# PICZone.net
KiCad netlist of a schematic drawn in Altium Designer
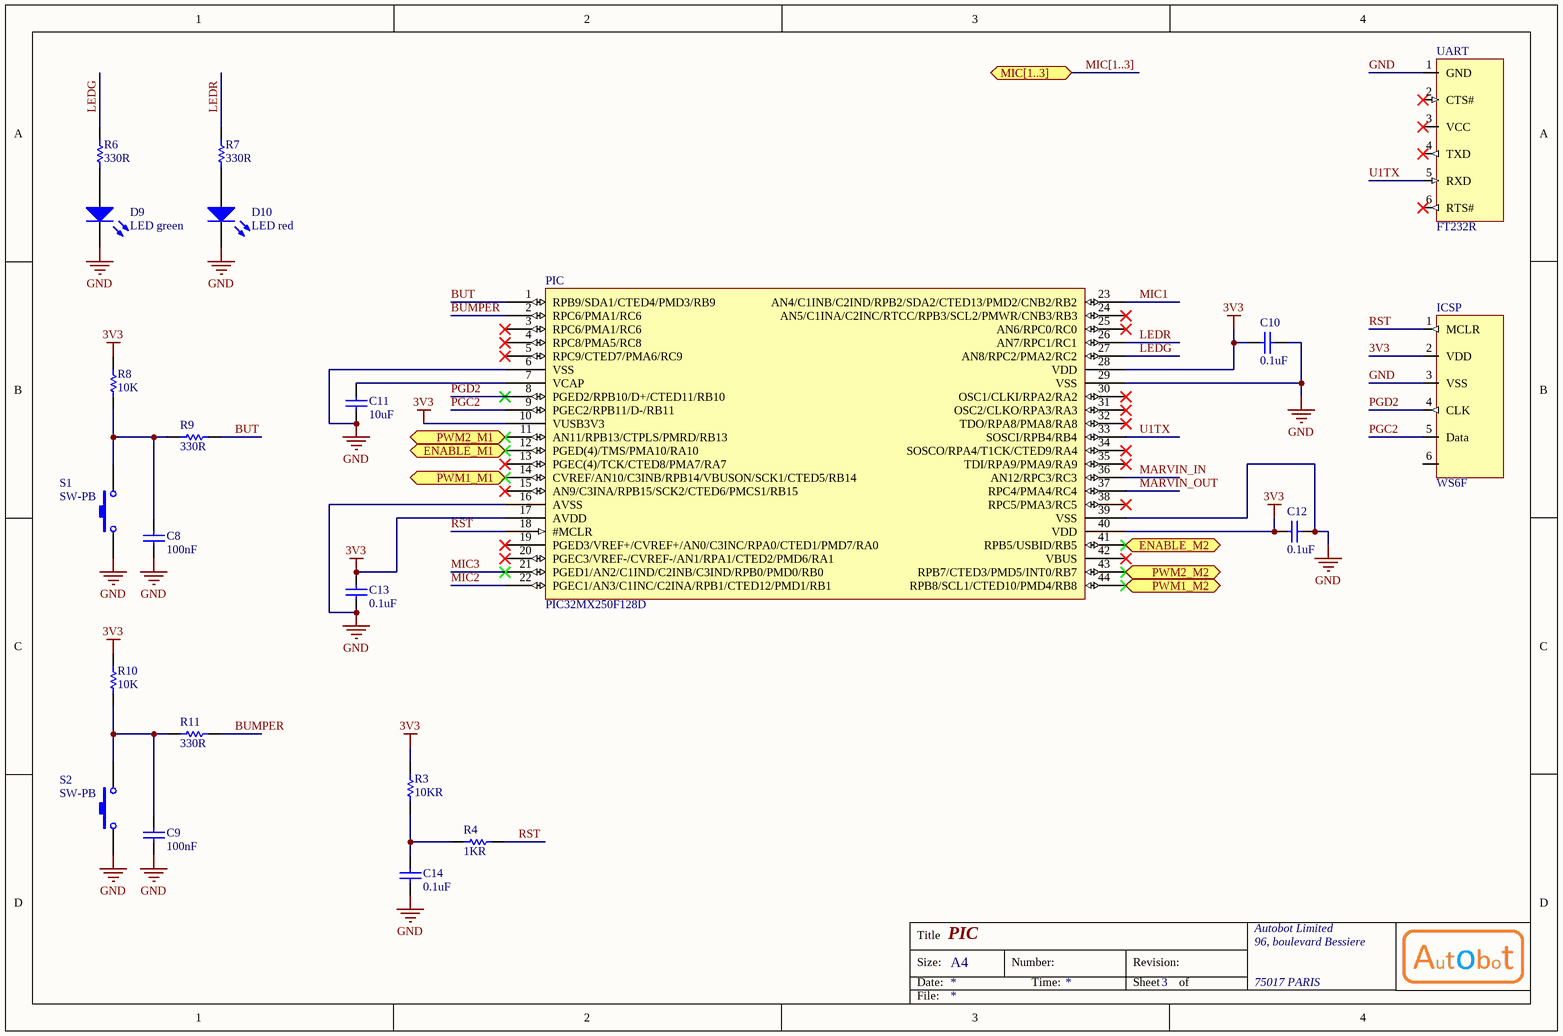
[diagram p0: PICZone.SchDoc]

(export (version "E")
  (design (tool "Eeschema 10.0.6"))
  (components
    (comp (ref "C8")
      (value "100nF")
      (footprint "CAPC1608N")
      (description "Capacitor")
      (fields (field (name "PUBLISHER") "Altium Limited"))
      (libsource (lib "Miscellaneous Devices") (part "Cap"))
    )
    (comp (ref "C9")
      (value "100nF")
      (footprint "CAPC1608N")
      (description "Capacitor")
      (fields (field (name "PUBLISHER") "Altium Limited"))
      (libsource (lib "Miscellaneous Devices") (part "Cap"))
    )
    (comp (ref "C10")
      (value "0.1uF")
      (footprint "CAPC1608N")
      (description "Capacitor")
      (fields (field (name "PUBLISHER") "Altium Limited"))
      (libsource (lib "Miscellaneous Devices") (part "Cap"))
    )
    (comp (ref "C11")
      (value "10uF")
      (footprint "CAPC1608N")
      (description "Capacitor")
      (fields (field (name "PUBLISHER") "Altium Limited"))
      (libsource (lib "Miscellaneous Devices") (part "Cap"))
    )
    (comp (ref "C12")
      (value "0.1uF")
      (footprint "CAPC1608N")
      (description "Capacitor")
      (fields (field (name "PUBLISHER") "Altium Limited"))
      (libsource (lib "Miscellaneous Devices") (part "Cap"))
    )
    (comp (ref "C13")
      (value "0.1uF")
      (footprint "CAPC1608N")
      (description "Capacitor")
      (fields (field (name "PUBLISHER") "Altium Limited"))
      (libsource (lib "Miscellaneous Devices") (part "Cap"))
    )
    (comp (ref "C14")
      (value "0.1uF")
      (footprint "CAPC1608N")
      (description "Capacitor")
      (fields (field (name "PUBLISHER") "Altium Limited"))
      (libsource (lib "Miscellaneous Devices") (part "Cap"))
    )
    (comp (ref "D9")
      (value "LED green")
      (footprint "LED1608")
      (description "Typical INFRARED GaAs LED")
      (fields (field (name "PUBLISHER") "Altium Limited"))
      (libsource (lib "Miscellaneous Devices") (part "LED0"))
    )
    (comp (ref "D10")
      (value "LED red")
      (footprint "LED1608")
      (description "Typical INFRARED GaAs LED")
      (fields (field (name "PUBLISHER") "Altium Limited"))
      (libsource (lib "Miscellaneous Devices") (part "LED0"))
    )
    (comp (ref "ICSP")
      (value "WS6F")
      (footprint "6-pin Connector")
      (libsource (lib "SCHLIB_Autobot") (part "WS6F"))
    )
    (comp (ref "PIC")
      (value "PIC32MX250F128D")
      (footprint "44TQFP")
      (libsource (lib "SCHLIB_Autobot") (part "PIC32MX250F128D"))
    )
    (comp (ref "R3")
      (value "10KR")
      (footprint "RESC1608N")
      (description "Resistor")
      (fields (field (name "PUBLISHER") "Altium Limited"))
      (libsource (lib "Miscellaneous Devices") (part "Res1"))
    )
    (comp (ref "R4")
      (value "1KR")
      (footprint "RESC1608N")
      (description "Resistor")
      (fields (field (name "PUBLISHER") "Altium Limited"))
      (libsource (lib "Miscellaneous Devices") (part "Res1"))
    )
    (comp (ref "R6")
      (value "330R")
      (footprint "RESC1608N")
      (description "Resistor")
      (fields (field (name "PUBLISHER") "Altium Limited"))
      (libsource (lib "Miscellaneous Devices") (part "Res1"))
    )
    (comp (ref "R7")
      (value "330R")
      (footprint "RESC1608N")
      (description "Resistor")
      (fields (field (name "PUBLISHER") "Altium Limited"))
      (libsource (lib "Miscellaneous Devices") (part "Res1"))
    )
    (comp (ref "R8")
      (value "10K")
      (footprint "RESC1608N")
      (description "Resistor")
      (fields (field (name "PUBLISHER") "Altium Limited"))
      (libsource (lib "Miscellaneous Devices") (part "Res1"))
    )
    (comp (ref "R9")
      (value "330R")
      (footprint "RESC1608N")
      (description "Resistor")
      (fields (field (name "PUBLISHER") "Altium Limited"))
      (libsource (lib "Miscellaneous Devices") (part "Res1"))
    )
    (comp (ref "R10")
      (value "10K")
      (footprint "RESC1608N")
      (description "Resistor")
      (fields (field (name "PUBLISHER") "Altium Limited"))
      (libsource (lib "Miscellaneous Devices") (part "Res1"))
    )
    (comp (ref "R11")
      (value "330R")
      (footprint "RESC1608N")
      (description "Resistor")
      (fields (field (name "PUBLISHER") "Altium Limited"))
      (libsource (lib "Miscellaneous Devices") (part "Res1"))
    )
    (comp (ref "S1")
      (value "SW-PB")
      (footprint "SPST-2")
      (description "Switch")
      (fields (field (name "PUBLISHER") "Altium Limited"))
      (libsource (lib "Miscellaneous Devices") (part "SW-PB"))
    )
    (comp (ref "S2")
      (value "SW-PB")
      (footprint "SPST-2")
      (description "Switch")
      (fields (field (name "PUBLISHER") "Altium Limited"))
      (libsource (lib "Miscellaneous Devices") (part "SW-PB"))
    )
    (comp (ref "UART")
      (value "FT232R")
      (footprint "6-pin Connector")
      (libsource (lib "SCHLIB_Autobot") (part "FT232R"))
    )
  )
  (nets
    (net (code "1") (name "/BUMPER") (class "Default")
      (node (ref "PIC") (pin "2") (pinfunction "RPC6/PMA1/RC6_2") (pintype "bidirectional"))
      (node (ref "R11") (pin "1") (pinfunction "1_1") (pintype "passive"))
    )
    (net (code "2") (name "/BUT") (class "Default")
      (node (ref "PIC") (pin "1") (pinfunction "RPB9/SDA1/CTED4/PMD3/RB9_1") (pintype "bidirectional"))
      (node (ref "R9") (pin "1") (pinfunction "1_1") (pintype "passive"))
    )
    (net (code "3") (name "/ENABLE_M1") (class "Default")
      (node (ref "PIC") (pin "12") (pinfunction "PGED(4)/TMS/PMA10/RA10_12") (pintype "bidirectional+no_connect"))
    )
    (net (code "4") (name "/ENABLE_M2") (class "Default")
      (node (ref "PIC") (pin "41") (pinfunction "RPB5/USBID/RB5_41") (pintype "bidirectional+no_connect"))
    )
    (net (code "5") (name "/LEDG") (class "Default")
      (node (ref "PIC") (pin "27") (pinfunction "AN8/RPC2/PMA2/RC2_27") (pintype "bidirectional"))
      (node (ref "R6") (pin "2") (pinfunction "2_2") (pintype "passive"))
    )
    (net (code "6") (name "/LEDR") (class "Default")
      (node (ref "PIC") (pin "26") (pinfunction "AN7/RPC1/RC1_26") (pintype "bidirectional"))
      (node (ref "R7") (pin "2") (pinfunction "2_2") (pintype "passive"))
    )
    (net (code "7") (name "/MARVIN_IN") (class "Default")
      (node (ref "PIC") (pin "36") (pinfunction "AN12/RPC3/RC3_36") (pintype "bidirectional"))
    )
    (net (code "8") (name "/MARVIN_OUT") (class "Default")
      (node (ref "PIC") (pin "37") (pinfunction "RPC4/PMA4/RC4_37") (pintype "bidirectional"))
    )
    (net (code "9") (name "/MIC1") (class "Default")
      (node (ref "PIC") (pin "23") (pinfunction "AN4/C1INB/C2IND/RPB2/SDA2/CTED13/PMD2/CNB2/RB2_23") (pintype "bidirectional"))
    )
    (net (code "10") (name "/MIC2") (class "Default")
      (node (ref "PIC") (pin "22") (pinfunction "PGEC1/AN3/C1INC/C2INA/RPB1/CTED12/PMD1/RB1_22") (pintype "bidirectional"))
    )
    (net (code "11") (name "/MIC3") (class "Default")
      (node (ref "PIC") (pin "21") (pinfunction "PGED1/AN2/C1IND/C2INB/C3IND/RPB0/PMD0/RB0_21") (pintype "bidirectional+no_connect"))
    )
    (net (code "13") (name "/PGC2") (class "Default")
      (node (ref "ICSP") (pin "5") (pinfunction "Data_5") (pintype "bidirectional"))
      (node (ref "PIC") (pin "9") (pinfunction "PGEC2/RPB11/D-/RB11_9") (pintype "bidirectional"))
    )
    (net (code "14") (name "/PGD2") (class "Default")
      (node (ref "ICSP") (pin "4") (pinfunction "CLK_4") (pintype "output"))
      (node (ref "PIC") (pin "8") (pinfunction "PGED2/RPB10/D+/CTED11/RB10_8") (pintype "bidirectional"))
    )
    (net (code "15") (name "/PWM1_M1") (class "Default")
      (node (ref "PIC") (pin "14") (pinfunction "CVREF/AN10/C3INB/RPB14/VBUSON/SCK1/CTED5/RB14_14") (pintype "bidirectional+no_connect"))
    )
    (net (code "16") (name "/PWM1_M2") (class "Default")
      (node (ref "PIC") (pin "44") (pinfunction "RPB8/SCL1/CTED10/PMD4/RB8_44") (pintype "bidirectional+no_connect"))
    )
    (net (code "17") (name "/PWM2_M1") (class "Default")
      (node (ref "PIC") (pin "11") (pinfunction "AN11/RPB13/CTPLS/PMRD/RB13_11") (pintype "bidirectional+no_connect"))
    )
    (net (code "18") (name "/PWM2_M2") (class "Default")
      (node (ref "PIC") (pin "43") (pinfunction "RPB7/CTED3/PMD5/INT0/RB7_43") (pintype "bidirectional+no_connect"))
    )
    (net (code "19") (name "/RST") (class "Default")
      (node (ref "ICSP") (pin "1") (pinfunction "MCLR_1") (pintype "output"))
      (node (ref "PIC") (pin "18") (pinfunction "#MCLR_18") (pintype "input"))
      (node (ref "R4") (pin "1") (pinfunction "1_1") (pintype "passive"))
    )
    (net (code "20") (name "/U1TX") (class "Default")
      (node (ref "PIC") (pin "33") (pinfunction "SOSCI/RPB4/RB4_33") (pintype "bidirectional"))
      (node (ref "UART") (pin "5") (pinfunction "RXD_5") (pintype "input"))
    )
    (net (code "21") (name "3V3") (class "Default")
      (node (ref "C10") (pin "2") (pinfunction "2_2") (pintype "passive"))
      (node (ref "C12") (pin "2") (pinfunction "2_2") (pintype "passive"))
      (node (ref "C13") (pin "1") (pinfunction "1_1") (pintype "passive"))
      (node (ref "ICSP") (pin "2") (pinfunction "VDD_2") (pintype "power_in"))
      (node (ref "PIC") (pin "10") (pinfunction "VUSB3V3_10") (pintype "passive"))
      (node (ref "PIC") (pin "17") (pinfunction "AVDD_17") (pintype "power_in"))
      (node (ref "PIC") (pin "28") (pinfunction "VDD_28") (pintype "power_in"))
      (node (ref "PIC") (pin "40") (pinfunction "VDD_40") (pintype "power_in"))
      (node (ref "R10") (pin "2") (pinfunction "2_2") (pintype "passive"))
      (node (ref "R3") (pin "1") (pinfunction "1_1") (pintype "passive"))
      (node (ref "R8") (pin "2") (pinfunction "2_2") (pintype "passive"))
    )
    (net (code "22") (name "GND") (class "Default")
      (node (ref "C10") (pin "1") (pinfunction "1_1") (pintype "passive"))
      (node (ref "C11") (pin "2") (pinfunction "2_2") (pintype "passive"))
      (node (ref "C12") (pin "1") (pinfunction "1_1") (pintype "passive"))
      (node (ref "C13") (pin "2") (pinfunction "2_2") (pintype "passive"))
      (node (ref "C14") (pin "1") (pinfunction "1_1") (pintype "passive"))
      (node (ref "C8") (pin "2") (pinfunction "2_2") (pintype "passive"))
      (node (ref "C9") (pin "2") (pinfunction "2_2") (pintype "passive"))
      (node (ref "D10") (pin "2") (pinfunction "K_2") (pintype "passive"))
      (node (ref "D9") (pin "2") (pinfunction "K_2") (pintype "passive"))
      (node (ref "ICSP") (pin "3") (pinfunction "VSS_3") (pintype "passive"))
      (node (ref "PIC") (pin "16") (pinfunction "AVSS_16") (pintype "passive"))
      (node (ref "PIC") (pin "29") (pinfunction "VSS_29") (pintype "passive"))
      (node (ref "PIC") (pin "39") (pinfunction "VSS_39") (pintype "passive"))
      (node (ref "PIC") (pin "6") (pinfunction "VSS_6") (pintype "passive"))
      (node (ref "S1") (pin "1") (pinfunction "1_1") (pintype "passive"))
      (node (ref "S2") (pin "1") (pinfunction "1_1") (pintype "passive"))
      (node (ref "UART") (pin "1") (pinfunction "GND_1") (pintype "passive"))
    )
    (net (code "23") (name "Net-(C8-Pad1)") (class "Default")
      (node (ref "C8") (pin "1") (pinfunction "1_1") (pintype "passive"))
      (node (ref "R8") (pin "1") (pinfunction "1_1") (pintype "passive"))
      (node (ref "R9") (pin "2") (pinfunction "2_2") (pintype "passive"))
      (node (ref "S1") (pin "2") (pinfunction "2_2") (pintype "passive"))
    )
    (net (code "24") (name "Net-(C9-Pad1)") (class "Default")
      (node (ref "C9") (pin "1") (pinfunction "1_1") (pintype "passive"))
      (node (ref "R10") (pin "1") (pinfunction "1_1") (pintype "passive"))
      (node (ref "R11") (pin "2") (pinfunction "2_2") (pintype "passive"))
      (node (ref "S2") (pin "2") (pinfunction "2_2") (pintype "passive"))
    )
    (net (code "25") (name "Net-(C14-Pad2)") (class "Default")
      (node (ref "C14") (pin "2") (pinfunction "2_2") (pintype "passive"))
      (node (ref "R3") (pin "2") (pinfunction "2_2") (pintype "passive"))
      (node (ref "R4") (pin "2") (pinfunction "2_2") (pintype "passive"))
    )
    (net (code "26") (name "Net-(D9-A)") (class "Default")
      (node (ref "D9") (pin "1") (pinfunction "A_1") (pintype "passive"))
      (node (ref "R6") (pin "1") (pinfunction "1_1") (pintype "passive"))
    )
    (net (code "27") (name "Net-(D10-A)") (class "Default")
      (node (ref "D10") (pin "1") (pinfunction "A_1") (pintype "passive"))
      (node (ref "R7") (pin "1") (pinfunction "1_1") (pintype "passive"))
    )
    (net (code "28") (name "Net-(PIC-VCAP)") (class "Default")
      (node (ref "C11") (pin "1") (pinfunction "1_1") (pintype "passive"))
      (node (ref "PIC") (pin "7") (pinfunction "VCAP_7") (pintype "power_in"))
    )
    (net (code "29") (name "unconnected-(ICSP-Pad6)") (class "Default")
      (node (ref "ICSP") (pin "6") (pintype "passive"))
    )
    (net (code "30") (name "unconnected-(PIC-AN5{slash}C1INA{slash}C2INC{slash}RTCC{slash}RPB3{slash}SCL2{slash}PMWR{slash}CNB3{slash}RB3-Pad24)") (class "Default")
      (node (ref "PIC") (pin "24") (pinfunction "AN5/C1INA/C2INC/RTCC/RPB3/SCL2/PMWR/CNB3/RB3_24") (pintype "bidirectional+no_connect"))
    )
    (net (code "31") (name "unconnected-(PIC-AN6{slash}RPC0{slash}RC0-Pad25)") (class "Default")
      (node (ref "PIC") (pin "25") (pinfunction "AN6/RPC0/RC0_25") (pintype "bidirectional+no_connect"))
    )
    (net (code "32") (name "unconnected-(PIC-AN9{slash}C3INA{slash}RPB15{slash}SCK2{slash}CTED6{slash}PMCS1{slash}RB15-Pad15)") (class "Default")
      (node (ref "PIC") (pin "15") (pinfunction "AN9/C3INA/RPB15/SCK2/CTED6/PMCS1/RB15_15") (pintype "bidirectional+no_connect"))
    )
    (net (code "33") (name "unconnected-(PIC-OSC1{slash}CLKI{slash}RPA2{slash}RA2-Pad30)") (class "Default")
      (node (ref "PIC") (pin "30") (pinfunction "OSC1/CLKI/RPA2/RA2_30") (pintype "bidirectional+no_connect"))
    )
    (net (code "34") (name "unconnected-(PIC-OSC2{slash}CLKO{slash}RPA3{slash}RA3-Pad31)") (class "Default")
      (node (ref "PIC") (pin "31") (pinfunction "OSC2/CLKO/RPA3/RA3_31") (pintype "bidirectional+no_connect"))
    )
    (net (code "35") (name "unconnected-(PIC-PGEC(4){slash}TCK{slash}CTED8{slash}PMA7{slash}RA7-Pad13)") (class "Default")
      (node (ref "PIC") (pin "13") (pinfunction "PGEC(4)/TCK/CTED8/PMA7/RA7_13") (pintype "bidirectional+no_connect"))
    )
    (net (code "36") (name "unconnected-(PIC-PGEC3{slash}VREF-{slash}CVREF-{slash}AN1{slash}RPA1{slash}CTED2{slash}PMD6{slash}RA1-Pad20)") (class "Default")
      (node (ref "PIC") (pin "20") (pinfunction "PGEC3/VREF-/CVREF-/AN1/RPA1/CTED2/PMD6/RA1_20") (pintype "bidirectional+no_connect"))
    )
    (net (code "37") (name "unconnected-(PIC-PGED3{slash}VREF+{slash}CVREF+{slash}AN0{slash}C3INC{slash}RPA0{slash}CTED1{slash}PMD7{slash}RA0-Pad19)") (class "Default")
      (node (ref "PIC") (pin "19") (pinfunction "PGED3/VREF+/CVREF+/AN0/C3INC/RPA0/CTED1/PMD7/RA0_19") (pintype "power_in+no_connect"))
    )
    (net (code "38") (name "unconnected-(PIC-RPC5{slash}PMA3{slash}RC5-Pad38)") (class "Default")
      (node (ref "PIC") (pin "38") (pinfunction "RPC5/PMA3/RC5_38") (pintype "bidirectional+no_connect"))
    )
    (net (code "39") (name "unconnected-(PIC-RPC6{slash}PMA1{slash}RC6-Pad3)") (class "Default")
      (node (ref "PIC") (pin "3") (pinfunction "RPC6/PMA1/RC6_3") (pintype "bidirectional+no_connect"))
    )
    (net (code "40") (name "unconnected-(PIC-RPC8{slash}PMA5{slash}RC8-Pad4)") (class "Default")
      (node (ref "PIC") (pin "4") (pinfunction "RPC8/PMA5/RC8_4") (pintype "bidirectional+no_connect"))
    )
    (net (code "41") (name "unconnected-(PIC-RPC9{slash}CTED7{slash}PMA6{slash}RC9-Pad5)") (class "Default")
      (node (ref "PIC") (pin "5") (pinfunction "RPC9/CTED7/PMA6/RC9_5") (pintype "bidirectional+no_connect"))
    )
    (net (code "42") (name "unconnected-(PIC-SOSCO{slash}RPA4{slash}T1CK{slash}CTED9{slash}RA4-Pad34)") (class "Default")
      (node (ref "PIC") (pin "34") (pinfunction "SOSCO/RPA4/T1CK/CTED9/RA4_34") (pintype "bidirectional+no_connect"))
    )
    (net (code "43") (name "unconnected-(PIC-TDI{slash}RPA9{slash}PMA9{slash}RA9-Pad35)") (class "Default")
      (node (ref "PIC") (pin "35") (pinfunction "TDI/RPA9/PMA9/RA9_35") (pintype "bidirectional+no_connect"))
    )
    (net (code "44") (name "unconnected-(PIC-TDO{slash}RPA8{slash}PMA8{slash}RA8-Pad32)") (class "Default")
      (node (ref "PIC") (pin "32") (pinfunction "TDO/RPA8/PMA8/RA8_32") (pintype "bidirectional+no_connect"))
    )
    (net (code "45") (name "unconnected-(PIC-VBUS-Pad42)") (class "Default")
      (node (ref "PIC") (pin "42") (pinfunction "VBUS_42") (pintype "passive+no_connect"))
    )
    (net (code "46") (name "unconnected-(UART-CTS#-Pad2)") (class "Default")
      (node (ref "UART") (pin "2") (pinfunction "CTS#_2") (pintype "input+no_connect"))
    )
    (net (code "47") (name "unconnected-(UART-RTS#-Pad6)") (class "Default")
      (node (ref "UART") (pin "6") (pinfunction "RTS#_6") (pintype "output+no_connect"))
    )
    (net (code "48") (name "unconnected-(UART-TXD-Pad4)") (class "Default")
      (node (ref "UART") (pin "4") (pinfunction "TXD_4") (pintype "output+no_connect"))
    )
    (net (code "49") (name "unconnected-(UART-VCC-Pad3)") (class "Default")
      (node (ref "UART") (pin "3") (pinfunction "VCC_3") (pintype "power_in+no_connect"))
    )
  )
)
